# Nu6509_vossi_v2.net
KiCad netlist of a schematic drawn in EAGLE
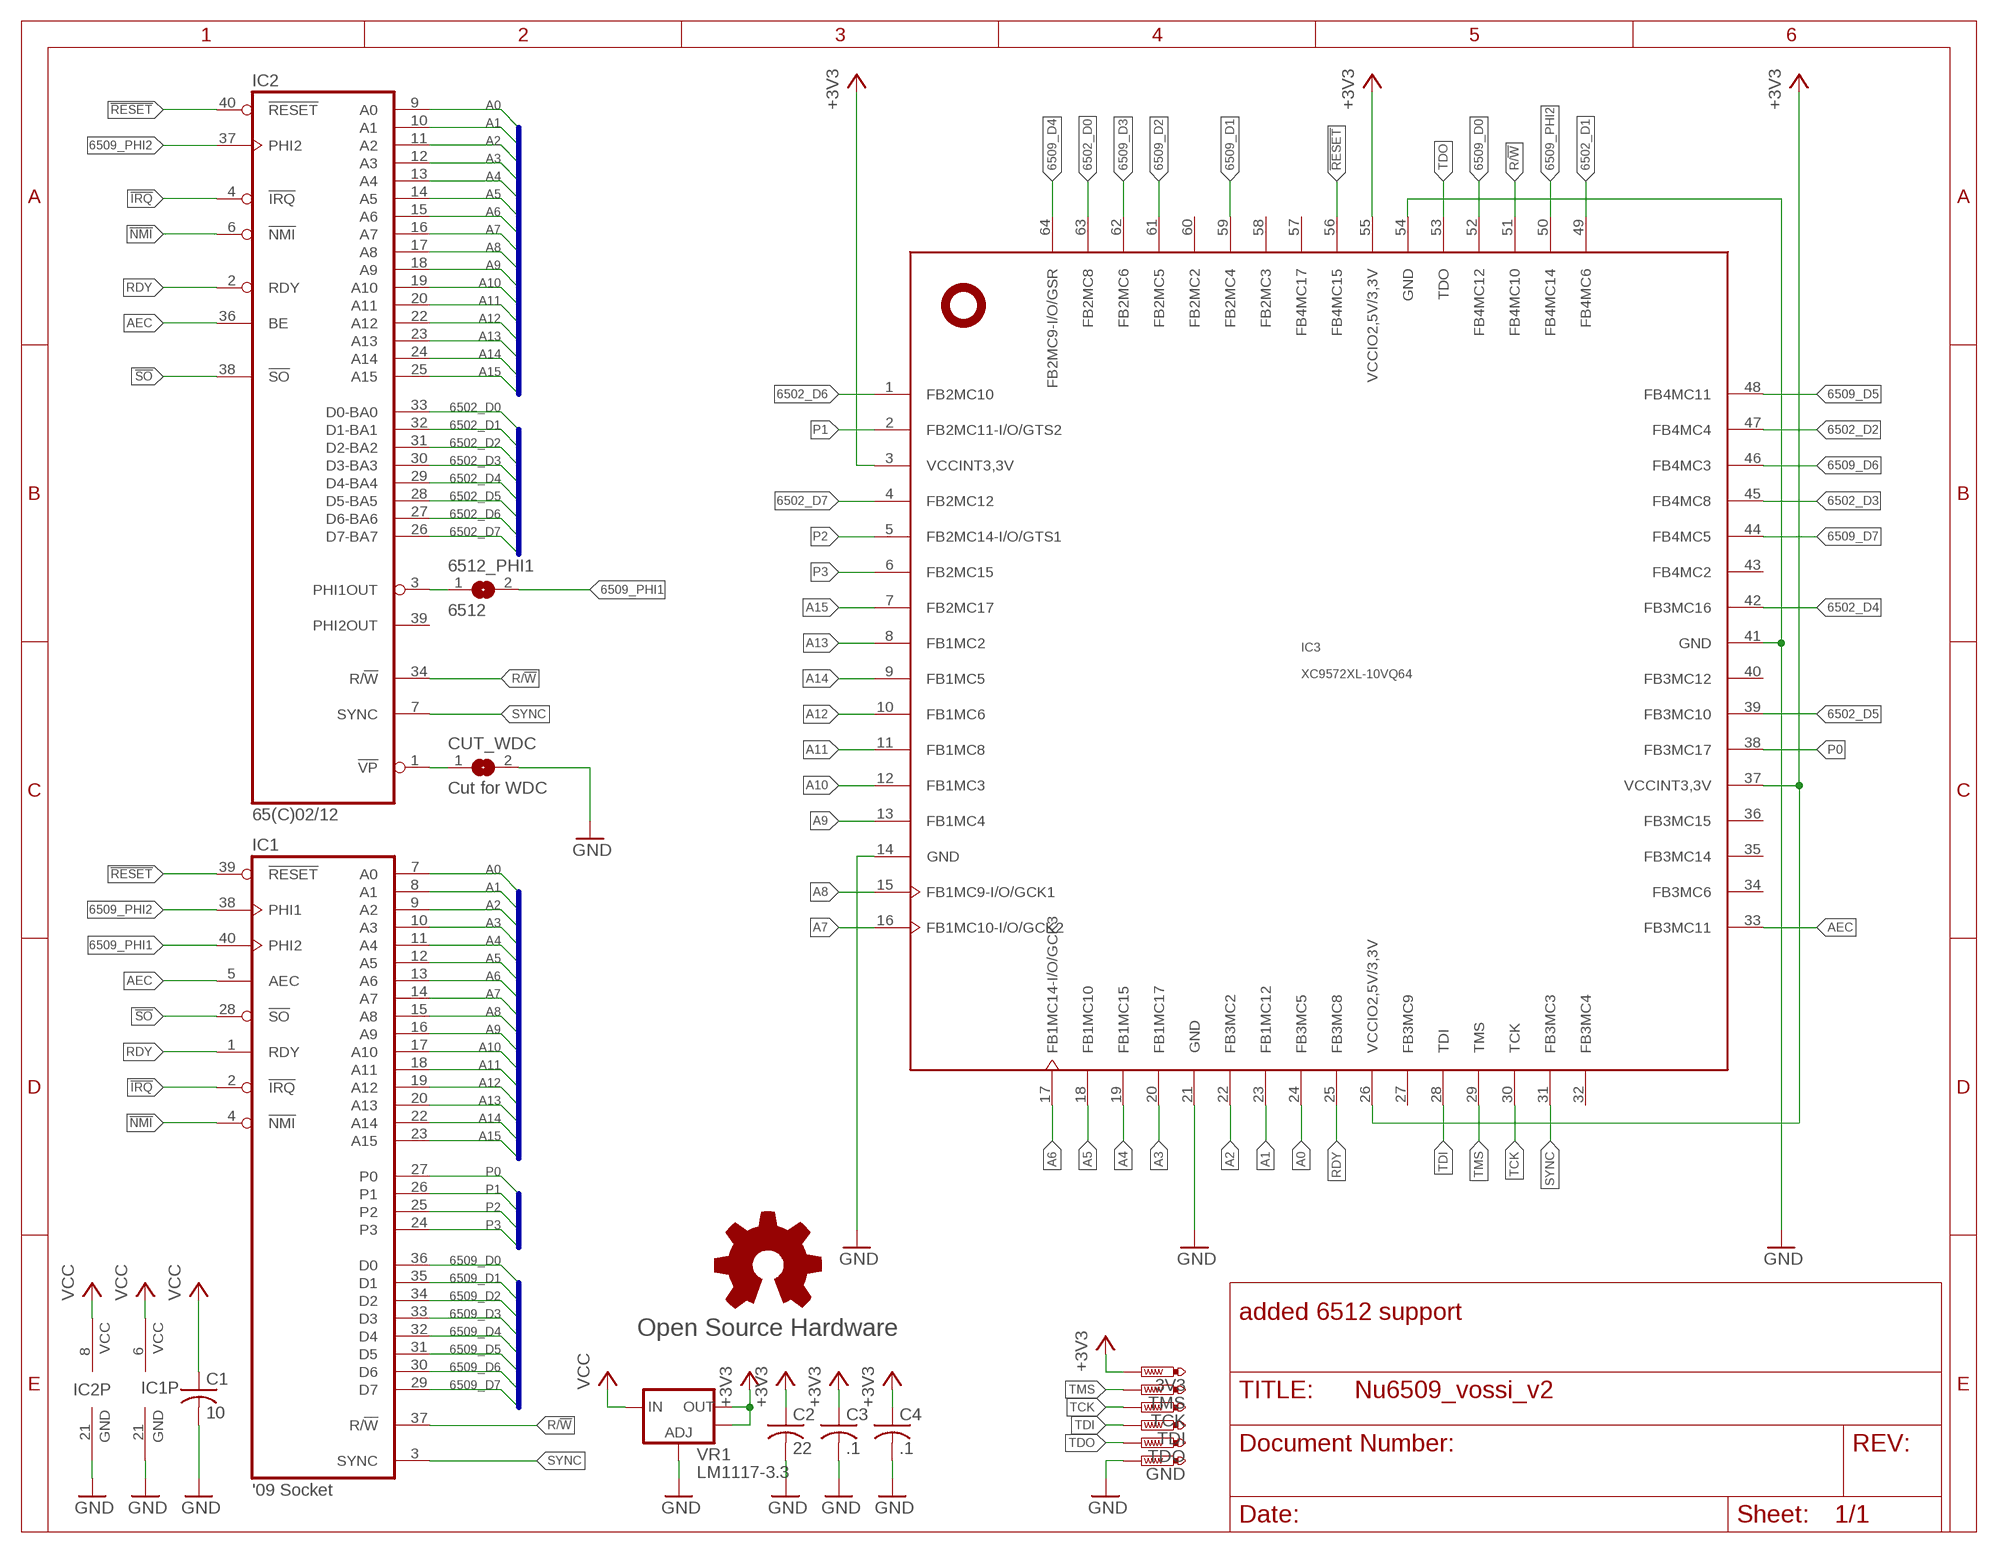
[diagram p0: schematic, sheet 1]

(export (version "E")
  (design (tool "Eeschema 10.0.6"))
  (components
    (comp (ref "3V3")
      (value "PTR1TP08R")
      (footprint "eagle-import:TP08R")
      (libsource (lib "eagle-import") (part "PTR1TP08R"))
    )
    (comp (ref "6512_PHI1")
      (value "6512")
      (footprint "eagle-import:SJ")
      (libsource (lib "eagle-import") (part "SJ"))
    )
    (comp (ref "C1")
      (value "10")
      (footprint "eagle-import:C0805")
      (libsource (lib "eagle-import") (part "C-USC0805"))
    )
    (comp (ref "C2")
      (value "22")
      (footprint "eagle-import:C0805")
      (libsource (lib "eagle-import") (part "C-USC0805"))
    )
    (comp (ref "C3")
      (value ".1")
      (footprint "eagle-import:C0805")
      (libsource (lib "eagle-import") (part "C-USC0805"))
    )
    (comp (ref "C4")
      (value ".1")
      (footprint "eagle-import:C0805")
      (libsource (lib "eagle-import") (part "C-USC0805"))
    )
    (comp (ref "CUT_WDC")
      (value "Cut for WDC")
      (footprint "eagle-import:SJ")
      (libsource (lib "eagle-import") (part "SJ"))
    )
    (comp (ref "GND")
      (value "PTR1TP08R")
      (footprint "eagle-import:TP08R")
      (libsource (lib "eagle-import") (part "PTR1TP08R"))
    )
    (comp (ref "GOLD_ORB_SM1")
      (value "Open Source Hardware")
      (footprint "eagle-import:OSHW_5MM")
      (libsource (lib "eagle-import") (part "OSHWLOGOLOGO5MM"))
    )
    (comp (ref "IC1")
      (value "'09 Socket")
      (footprint "eagle-import:DIL40-ROUNDPAD")
      (libsource (lib "eagle-import") (part "6509-RP"))
    )
    (comp (ref "IC2")
      (value "65(C)02/12")
      (footprint "eagle-import:DIL40-ROUNDPAD")
      (libsource (lib "eagle-import") (part "W65C02S-RP"))
    )
    (comp (ref "IC3")
      (value "XC9572XL-10VQ64")
      (footprint "eagle-import:VQFP64")
      (libsource (lib "eagle-import") (part "XC9572XLVQG64"))
    )
    (comp (ref "TCK")
      (value "PTR1TP08R")
      (footprint "eagle-import:TP08R")
      (libsource (lib "eagle-import") (part "PTR1TP08R"))
    )
    (comp (ref "TDI")
      (value "PTR1TP08R")
      (footprint "eagle-import:TP08R")
      (libsource (lib "eagle-import") (part "PTR1TP08R"))
    )
    (comp (ref "TDO")
      (value "PTR1TP08R")
      (footprint "eagle-import:TP08R")
      (libsource (lib "eagle-import") (part "PTR1TP08R"))
    )
    (comp (ref "TMS")
      (value "PTR1TP08R")
      (footprint "eagle-import:TP08R")
      (libsource (lib "eagle-import") (part "PTR1TP08R"))
    )
    (comp (ref "VR1")
      (value "LM1117-3.3")
      (footprint "eagle-import:SOT223")
      (libsource (lib "eagle-import") (part "V_REG_LM1117SOT223"))
    )
  )
  (nets
    (net (code "1") (name "+3V3") (class "Default")
      (node (ref "3V3") (pin "TP") (pinfunction "TP_TP") (pintype "input"))
      (node (ref "C2") (pin "1") (pinfunction "1_1") (pintype "passive"))
      (node (ref "C3") (pin "1") (pinfunction "1_1") (pintype "passive"))
      (node (ref "C4") (pin "1") (pinfunction "1_1") (pintype "passive"))
      (node (ref "IC3") (pin "26") (pinfunction "VCCIO2,5V/3,3V_26") (pintype "power_in"))
      (node (ref "IC3") (pin "3") (pinfunction "VCCINT3,3V_3") (pintype "power_in"))
      (node (ref "IC3") (pin "37") (pinfunction "VCCINT3,3V_37") (pintype "power_in"))
      (node (ref "IC3") (pin "55") (pinfunction "VCCIO2,5V/3,3V_55") (pintype "power_in"))
      (node (ref "VR1") (pin "2") (pinfunction "OUT_2") (pintype "output"))
      (node (ref "VR1") (pin "4") (pinfunction "OUT_4") (pintype "output"))
    )
    (net (code "2") (name "/R{slash}~{W}") (class "Default")
      (node (ref "IC1") (pin "37") (pinfunction "R/~{W}_37") (pintype "output"))
      (node (ref "IC2") (pin "34") (pinfunction "R/~{W}_34") (pintype "output"))
      (node (ref "IC3") (pin "51") (pinfunction "FB4MC10_51") (pintype "bidirectional"))
    )
    (net (code "3") (name "/~{IRQ}") (class "Default")
      (node (ref "IC1") (pin "2") (pinfunction "~{IRQ}_2") (pintype "input"))
      (node (ref "IC2") (pin "4") (pinfunction "~{IRQ}_4") (pintype "input"))
    )
    (net (code "4") (name "/~{NMI}") (class "Default")
      (node (ref "IC1") (pin "4") (pinfunction "~{NMI}_4") (pintype "input"))
      (node (ref "IC2") (pin "6") (pinfunction "~{NMI}_6") (pintype "input"))
    )
    (net (code "5") (name "/~{RESET}") (class "Default")
      (node (ref "IC1") (pin "39") (pinfunction "~{RESET}_39") (pintype "input"))
      (node (ref "IC2") (pin "40") (pinfunction "~{RESET}_40") (pintype "input"))
      (node (ref "IC3") (pin "56") (pinfunction "FB4MC15_56") (pintype "bidirectional"))
    )
    (net (code "6") (name "/~{SO}") (class "Default")
      (node (ref "IC1") (pin "28") (pinfunction "~{SO}_28") (pintype "input"))
      (node (ref "IC2") (pin "38") (pinfunction "~{SO}_38") (pintype "output"))
    )
    (net (code "7") (name "6502_D0") (class "Default")
      (node (ref "IC2") (pin "33") (pinfunction "D0-BA0_33") (pintype "bidirectional"))
      (node (ref "IC3") (pin "63") (pinfunction "FB2MC8_63") (pintype "bidirectional"))
    )
    (net (code "8") (name "6502_D1") (class "Default")
      (node (ref "IC2") (pin "32") (pinfunction "D1-BA1_32") (pintype "bidirectional"))
      (node (ref "IC3") (pin "49") (pinfunction "FB4MC6_49") (pintype "bidirectional"))
    )
    (net (code "9") (name "6502_D2") (class "Default")
      (node (ref "IC2") (pin "31") (pinfunction "D2-BA2_31") (pintype "bidirectional"))
      (node (ref "IC3") (pin "47") (pinfunction "FB4MC4_47") (pintype "bidirectional"))
    )
    (net (code "10") (name "6502_D3") (class "Default")
      (node (ref "IC2") (pin "30") (pinfunction "D3-BA3_30") (pintype "bidirectional"))
      (node (ref "IC3") (pin "45") (pinfunction "FB4MC8_45") (pintype "bidirectional"))
    )
    (net (code "11") (name "6502_D4") (class "Default")
      (node (ref "IC2") (pin "29") (pinfunction "D4-BA4_29") (pintype "bidirectional"))
      (node (ref "IC3") (pin "42") (pinfunction "FB3MC16_42") (pintype "bidirectional"))
    )
    (net (code "12") (name "6502_D5") (class "Default")
      (node (ref "IC2") (pin "28") (pinfunction "D5-BA5_28") (pintype "bidirectional"))
      (node (ref "IC3") (pin "39") (pinfunction "FB3MC10_39") (pintype "bidirectional"))
    )
    (net (code "13") (name "6502_D6") (class "Default")
      (node (ref "IC2") (pin "27") (pinfunction "D6-BA6_27") (pintype "bidirectional"))
      (node (ref "IC3") (pin "1") (pinfunction "FB2MC10_1") (pintype "bidirectional"))
    )
    (net (code "14") (name "6502_D7") (class "Default")
      (node (ref "IC2") (pin "26") (pinfunction "D7-BA7_26") (pintype "bidirectional"))
      (node (ref "IC3") (pin "4") (pinfunction "FB2MC12_4") (pintype "bidirectional"))
    )
    (net (code "15") (name "6509_D0") (class "Default")
      (node (ref "IC1") (pin "36") (pinfunction "D0_36") (pintype "bidirectional"))
      (node (ref "IC3") (pin "52") (pinfunction "FB4MC12_52") (pintype "bidirectional"))
    )
    (net (code "16") (name "6509_D1") (class "Default")
      (node (ref "IC1") (pin "35") (pinfunction "D1_35") (pintype "bidirectional"))
      (node (ref "IC3") (pin "59") (pinfunction "FB2MC4_59") (pintype "bidirectional"))
    )
    (net (code "17") (name "6509_D2") (class "Default")
      (node (ref "IC1") (pin "34") (pinfunction "D2_34") (pintype "bidirectional"))
      (node (ref "IC3") (pin "61") (pinfunction "FB2MC5_61") (pintype "bidirectional"))
    )
    (net (code "18") (name "6509_D3") (class "Default")
      (node (ref "IC1") (pin "33") (pinfunction "D3_33") (pintype "bidirectional"))
      (node (ref "IC3") (pin "62") (pinfunction "FB2MC6_62") (pintype "bidirectional"))
    )
    (net (code "19") (name "6509_D4") (class "Default")
      (node (ref "IC1") (pin "32") (pinfunction "D4_32") (pintype "bidirectional"))
      (node (ref "IC3") (pin "64") (pinfunction "FB2MC9-I/O/GSR_64") (pintype "bidirectional"))
    )
    (net (code "20") (name "6509_D5") (class "Default")
      (node (ref "IC1") (pin "31") (pinfunction "D5_31") (pintype "bidirectional"))
      (node (ref "IC3") (pin "48") (pinfunction "FB4MC11_48") (pintype "bidirectional"))
    )
    (net (code "21") (name "6509_D6") (class "Default")
      (node (ref "IC1") (pin "30") (pinfunction "D6_30") (pintype "bidirectional"))
      (node (ref "IC3") (pin "46") (pinfunction "FB4MC3_46") (pintype "bidirectional"))
    )
    (net (code "22") (name "6509_D7") (class "Default")
      (node (ref "IC1") (pin "29") (pinfunction "D7_29") (pintype "bidirectional"))
      (node (ref "IC3") (pin "44") (pinfunction "FB4MC5_44") (pintype "bidirectional"))
    )
    (net (code "23") (name "6509_PHI1") (class "Default")
      (node (ref "6512_PHI1") (pin "2") (pinfunction "2_2") (pintype "passive"))
      (node (ref "IC1") (pin "40") (pinfunction "PHI2_40") (pintype "input"))
    )
    (net (code "24") (name "6509_PHI2") (class "Default")
      (node (ref "IC1") (pin "38") (pinfunction "PHI1_38") (pintype "input"))
      (node (ref "IC2") (pin "37") (pinfunction "PHI2_37") (pintype "input"))
      (node (ref "IC3") (pin "50") (pinfunction "FB4MC14_50") (pintype "bidirectional"))
    )
    (net (code "25") (name "A0") (class "Default")
      (node (ref "IC1") (pin "7") (pinfunction "A0_7") (pintype "output"))
      (node (ref "IC2") (pin "9") (pinfunction "A0_9") (pintype "tri_state"))
      (node (ref "IC3") (pin "24") (pinfunction "FB3MC5_24") (pintype "bidirectional"))
    )
    (net (code "26") (name "A1") (class "Default")
      (node (ref "IC1") (pin "8") (pinfunction "A1_8") (pintype "output"))
      (node (ref "IC2") (pin "10") (pinfunction "A1_10") (pintype "tri_state"))
      (node (ref "IC3") (pin "23") (pinfunction "FB1MC12_23") (pintype "bidirectional"))
    )
    (net (code "27") (name "A2") (class "Default")
      (node (ref "IC1") (pin "9") (pinfunction "A2_9") (pintype "output"))
      (node (ref "IC2") (pin "11") (pinfunction "A2_11") (pintype "tri_state"))
      (node (ref "IC3") (pin "22") (pinfunction "FB3MC2_22") (pintype "bidirectional"))
    )
    (net (code "28") (name "A3") (class "Default")
      (node (ref "IC1") (pin "10") (pinfunction "A3_10") (pintype "output"))
      (node (ref "IC2") (pin "12") (pinfunction "A3_12") (pintype "tri_state"))
      (node (ref "IC3") (pin "20") (pinfunction "FB1MC17_20") (pintype "bidirectional"))
    )
    (net (code "29") (name "A4") (class "Default")
      (node (ref "IC1") (pin "11") (pinfunction "A4_11") (pintype "output"))
      (node (ref "IC2") (pin "13") (pinfunction "A4_13") (pintype "tri_state"))
      (node (ref "IC3") (pin "19") (pinfunction "FB1MC15_19") (pintype "bidirectional"))
    )
    (net (code "30") (name "A5") (class "Default")
      (node (ref "IC1") (pin "12") (pinfunction "A5_12") (pintype "output"))
      (node (ref "IC2") (pin "14") (pinfunction "A5_14") (pintype "tri_state"))
      (node (ref "IC3") (pin "18") (pinfunction "FB1MC10_18") (pintype "bidirectional"))
    )
    (net (code "31") (name "A6") (class "Default")
      (node (ref "IC1") (pin "13") (pinfunction "A6_13") (pintype "output"))
      (node (ref "IC2") (pin "15") (pinfunction "A6_15") (pintype "tri_state"))
      (node (ref "IC3") (pin "17") (pinfunction "FB1MC14-I/O/GCK3_17") (pintype "bidirectional"))
    )
    (net (code "32") (name "A7") (class "Default")
      (node (ref "IC1") (pin "14") (pinfunction "A7_14") (pintype "output"))
      (node (ref "IC2") (pin "16") (pinfunction "A7_16") (pintype "tri_state"))
      (node (ref "IC3") (pin "16") (pinfunction "FB1MC10-I/O/GCK2_16") (pintype "bidirectional"))
    )
    (net (code "33") (name "A8") (class "Default")
      (node (ref "IC1") (pin "15") (pinfunction "A8_15") (pintype "output"))
      (node (ref "IC2") (pin "17") (pinfunction "A8_17") (pintype "tri_state"))
      (node (ref "IC3") (pin "15") (pinfunction "FB1MC9-I/O/GCK1_15") (pintype "bidirectional"))
    )
    (net (code "34") (name "A9") (class "Default")
      (node (ref "IC1") (pin "16") (pinfunction "A9_16") (pintype "output"))
      (node (ref "IC2") (pin "18") (pinfunction "A9_18") (pintype "tri_state"))
      (node (ref "IC3") (pin "13") (pinfunction "FB1MC4_13") (pintype "bidirectional"))
    )
    (net (code "35") (name "A10") (class "Default")
      (node (ref "IC1") (pin "17") (pinfunction "A10_17") (pintype "output"))
      (node (ref "IC2") (pin "19") (pinfunction "A10_19") (pintype "tri_state"))
      (node (ref "IC3") (pin "12") (pinfunction "FB1MC3_12") (pintype "bidirectional"))
    )
    (net (code "36") (name "A11") (class "Default")
      (node (ref "IC1") (pin "18") (pinfunction "A11_18") (pintype "output"))
      (node (ref "IC2") (pin "20") (pinfunction "A11_20") (pintype "tri_state"))
      (node (ref "IC3") (pin "11") (pinfunction "FB1MC8_11") (pintype "bidirectional"))
    )
    (net (code "37") (name "A12") (class "Default")
      (node (ref "IC1") (pin "19") (pinfunction "A12_19") (pintype "output"))
      (node (ref "IC2") (pin "22") (pinfunction "A12_22") (pintype "tri_state"))
      (node (ref "IC3") (pin "10") (pinfunction "FB1MC6_10") (pintype "bidirectional"))
    )
    (net (code "38") (name "A13") (class "Default")
      (node (ref "IC1") (pin "20") (pinfunction "A13_20") (pintype "output"))
      (node (ref "IC2") (pin "23") (pinfunction "A13_23") (pintype "tri_state"))
      (node (ref "IC3") (pin "8") (pinfunction "FB1MC2_8") (pintype "bidirectional"))
    )
    (net (code "39") (name "A14") (class "Default")
      (node (ref "IC1") (pin "22") (pinfunction "A14_22") (pintype "output"))
      (node (ref "IC2") (pin "24") (pinfunction "A14_24") (pintype "tri_state"))
      (node (ref "IC3") (pin "9") (pinfunction "FB1MC5_9") (pintype "bidirectional"))
    )
    (net (code "40") (name "A15") (class "Default")
      (node (ref "IC1") (pin "23") (pinfunction "A15_23") (pintype "output"))
      (node (ref "IC2") (pin "25") (pinfunction "A15_25") (pintype "tri_state"))
      (node (ref "IC3") (pin "7") (pinfunction "FB2MC17_7") (pintype "bidirectional"))
    )
    (net (code "41") (name "AEC") (class "Default")
      (node (ref "IC1") (pin "5") (pinfunction "AEC_5") (pintype "input"))
      (node (ref "IC2") (pin "36") (pinfunction "BE_36") (pintype "input"))
      (node (ref "IC3") (pin "33") (pinfunction "FB3MC11_33") (pintype "bidirectional"))
    )
    (net (code "42") (name "GND") (class "Default")
      (node (ref "C1") (pin "2") (pinfunction "2_2") (pintype "passive"))
      (node (ref "C2") (pin "2") (pinfunction "2_2") (pintype "passive"))
      (node (ref "C3") (pin "2") (pinfunction "2_2") (pintype "passive"))
      (node (ref "C4") (pin "2") (pinfunction "2_2") (pintype "passive"))
      (node (ref "CUT_WDC") (pin "2") (pinfunction "2_2") (pintype "passive"))
      (node (ref "GND") (pin "TP") (pinfunction "TP_TP") (pintype "input"))
      (node (ref "IC1") (pin "21") (pinfunction "GND_21") (pintype "power_in"))
      (node (ref "IC2") (pin "21") (pinfunction "GND_21") (pintype "power_in"))
      (node (ref "IC3") (pin "14") (pinfunction "GND_14") (pintype "power_in"))
      (node (ref "IC3") (pin "21") (pinfunction "GND_21") (pintype "power_in"))
      (node (ref "IC3") (pin "41") (pinfunction "GND_41") (pintype "power_in"))
      (node (ref "IC3") (pin "54") (pinfunction "GND_54") (pintype "power_in"))
      (node (ref "VR1") (pin "1") (pinfunction "ADJ_1") (pintype "input"))
    )
    (net (code "43") (name "Net-(IC2A-PHI1OUT)") (class "Default")
      (node (ref "6512_PHI1") (pin "1") (pinfunction "1_1") (pintype "passive"))
      (node (ref "IC2") (pin "3") (pinfunction "PHI1OUT_3") (pintype "input"))
    )
    (net (code "44") (name "Net-(IC2A-~{VP})") (class "Default")
      (node (ref "CUT_WDC") (pin "1") (pinfunction "1_1") (pintype "passive"))
      (node (ref "IC2") (pin "1") (pinfunction "~{VP}_1") (pintype "output"))
    )
    (net (code "45") (name "P0") (class "Default")
      (node (ref "IC1") (pin "27") (pinfunction "P0_27") (pintype "output"))
      (node (ref "IC3") (pin "38") (pinfunction "FB3MC17_38") (pintype "bidirectional"))
    )
    (net (code "46") (name "P1") (class "Default")
      (node (ref "IC1") (pin "26") (pinfunction "P1_26") (pintype "output"))
      (node (ref "IC3") (pin "2") (pinfunction "FB2MC11-I/O/GTS2_2") (pintype "bidirectional"))
    )
    (net (code "47") (name "P2") (class "Default")
      (node (ref "IC1") (pin "25") (pinfunction "P2_25") (pintype "output"))
      (node (ref "IC3") (pin "5") (pinfunction "FB2MC14-I/O/GTS1_5") (pintype "bidirectional"))
    )
    (net (code "48") (name "P3") (class "Default")
      (node (ref "IC1") (pin "24") (pinfunction "P3_24") (pintype "output"))
      (node (ref "IC3") (pin "6") (pinfunction "FB2MC15_6") (pintype "bidirectional"))
    )
    (net (code "49") (name "RDY") (class "Default")
      (node (ref "IC1") (pin "1") (pinfunction "RDY_1") (pintype "input"))
      (node (ref "IC2") (pin "2") (pinfunction "RDY_2") (pintype "bidirectional"))
      (node (ref "IC3") (pin "25") (pinfunction "FB3MC8_25") (pintype "bidirectional"))
    )
    (net (code "50") (name "SYNC") (class "Default")
      (node (ref "IC1") (pin "3") (pinfunction "SYNC_3") (pintype "output"))
      (node (ref "IC2") (pin "7") (pinfunction "SYNC_7") (pintype "output"))
      (node (ref "IC3") (pin "31") (pinfunction "FB3MC3_31") (pintype "bidirectional"))
    )
    (net (code "51") (name "TCK") (class "Default")
      (node (ref "IC3") (pin "30") (pinfunction "TCK_30") (pintype "bidirectional"))
      (node (ref "TCK") (pin "TP") (pinfunction "TP_TP") (pintype "input"))
    )
    (net (code "52") (name "TDI") (class "Default")
      (node (ref "IC3") (pin "28") (pinfunction "TDI_28") (pintype "bidirectional"))
      (node (ref "TDI") (pin "TP") (pinfunction "TP_TP") (pintype "input"))
    )
    (net (code "53") (name "TDO") (class "Default")
      (node (ref "IC3") (pin "53") (pinfunction "TDO_53") (pintype "bidirectional"))
      (node (ref "TDO") (pin "TP") (pinfunction "TP_TP") (pintype "input"))
    )
    (net (code "54") (name "TMS") (class "Default")
      (node (ref "IC3") (pin "29") (pinfunction "TMS_29") (pintype "bidirectional"))
      (node (ref "TMS") (pin "TP") (pinfunction "TP_TP") (pintype "input"))
    )
    (net (code "55") (name "VCC") (class "Default")
      (node (ref "C1") (pin "1") (pinfunction "1_1") (pintype "passive"))
      (node (ref "IC1") (pin "6") (pinfunction "VCC_6") (pintype "power_in"))
      (node (ref "IC2") (pin "8") (pinfunction "VCC_8") (pintype "power_in"))
      (node (ref "VR1") (pin "3") (pinfunction "IN_3") (pintype "input"))
    )
    (net (code "56") (name "unconnected-(IC2A-PHI2OUT-Pad39)") (class "Default")
      (node (ref "IC2") (pin "39") (pinfunction "PHI2OUT_39") (pintype "output"))
    )
    (net (code "57") (name "unconnected-(IC3-FB2MC2-Pad60)") (class "Default")
      (node (ref "IC3") (pin "60") (pinfunction "FB2MC2_60") (pintype "bidirectional"))
    )
    (net (code "58") (name "unconnected-(IC3-FB2MC3-Pad58)") (class "Default")
      (node (ref "IC3") (pin "58") (pinfunction "FB2MC3_58") (pintype "bidirectional"))
    )
    (net (code "59") (name "unconnected-(IC3-FB3MC4-Pad32)") (class "Default")
      (node (ref "IC3") (pin "32") (pinfunction "FB3MC4_32") (pintype "bidirectional"))
    )
    (net (code "60") (name "unconnected-(IC3-FB3MC6-Pad34)") (class "Default")
      (node (ref "IC3") (pin "34") (pinfunction "FB3MC6_34") (pintype "bidirectional"))
    )
    (net (code "61") (name "unconnected-(IC3-FB3MC9-Pad27)") (class "Default")
      (node (ref "IC3") (pin "27") (pinfunction "FB3MC9_27") (pintype "bidirectional"))
    )
    (net (code "62") (name "unconnected-(IC3-FB3MC12-Pad40)") (class "Default")
      (node (ref "IC3") (pin "40") (pinfunction "FB3MC12_40") (pintype "bidirectional"))
    )
    (net (code "63") (name "unconnected-(IC3-FB3MC14-Pad35)") (class "Default")
      (node (ref "IC3") (pin "35") (pinfunction "FB3MC14_35") (pintype "bidirectional"))
    )
    (net (code "64") (name "unconnected-(IC3-FB3MC15-Pad36)") (class "Default")
      (node (ref "IC3") (pin "36") (pinfunction "FB3MC15_36") (pintype "bidirectional"))
    )
    (net (code "65") (name "unconnected-(IC3-FB4MC2-Pad43)") (class "Default")
      (node (ref "IC3") (pin "43") (pinfunction "FB4MC2_43") (pintype "bidirectional"))
    )
    (net (code "66") (name "unconnected-(IC3-FB4MC17-Pad57)") (class "Default")
      (node (ref "IC3") (pin "57") (pinfunction "FB4MC17_57") (pintype "bidirectional"))
    )
  )
)
